# 6301_Lab3_Main.net
KiCad netlist of a schematic drawn in Altium Designer
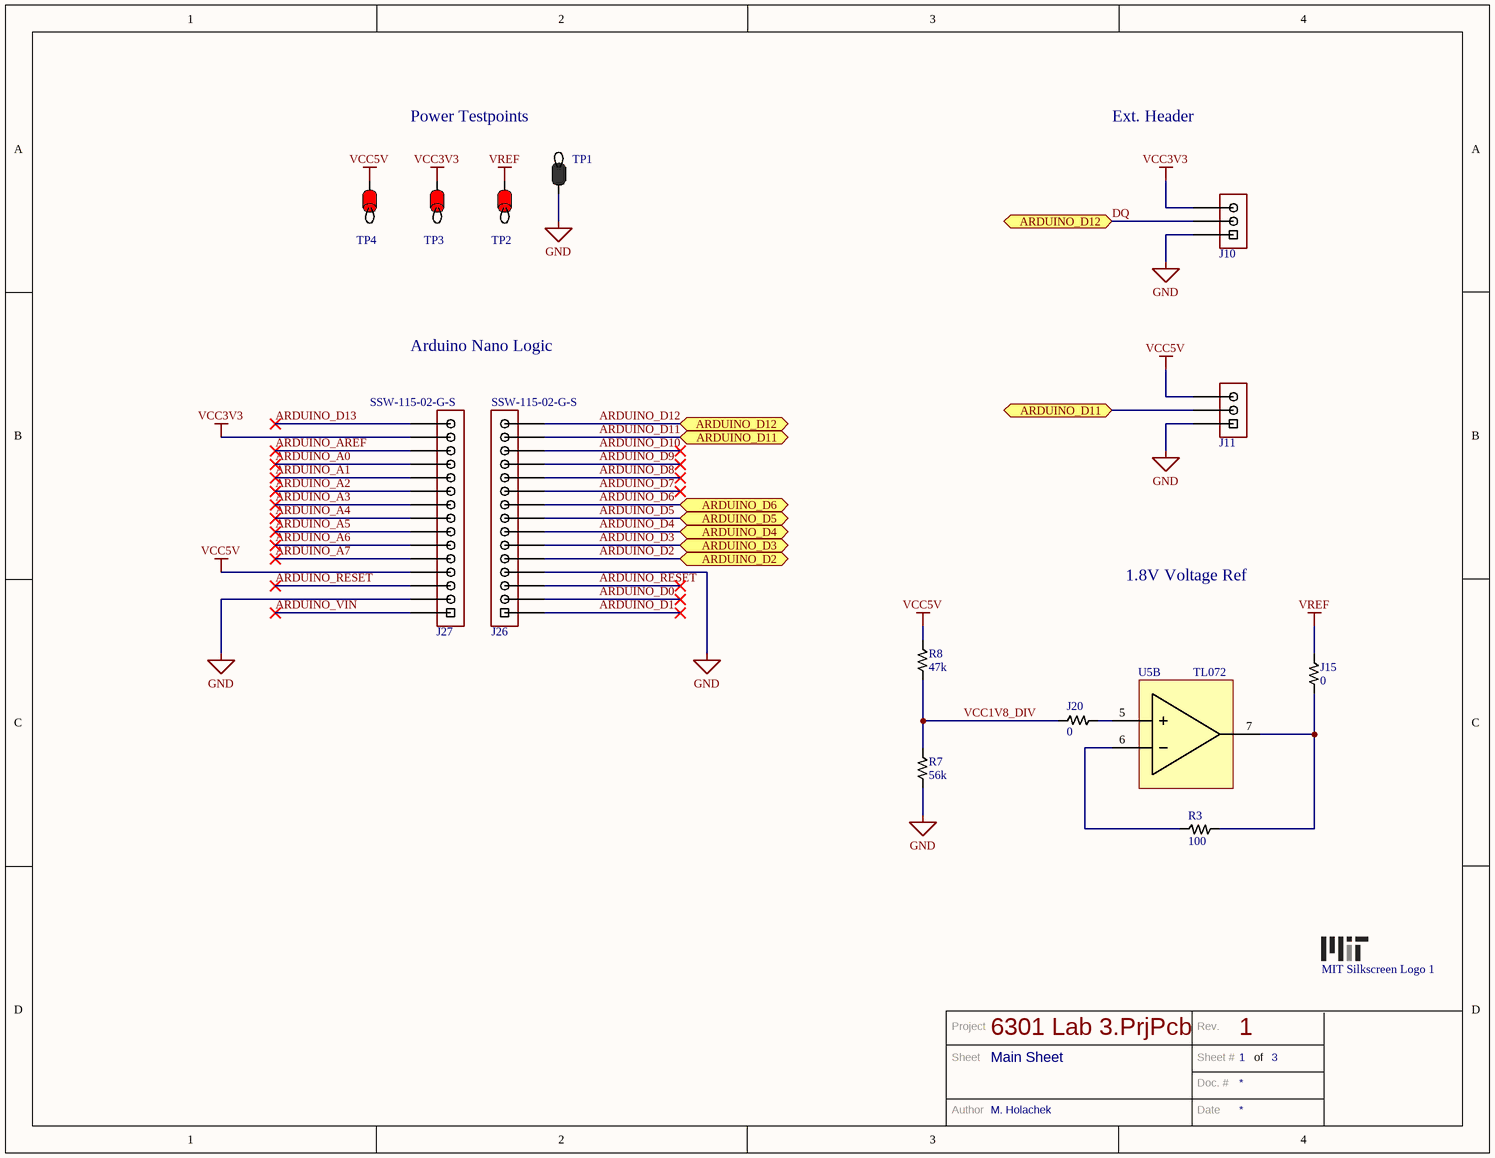
[diagram p0: 6301 Lab3 Main.SchDoc]

(export (version "E")
  (design (tool "Eeschema 10.0.6"))
  (components
    (comp (ref "J10")
      (value "Short")
      (footprint "1X03")
      (description "1x3 2.54mm Standard Connector")
      (libsource (lib "6301 Lab 3") (part "1x3"))
    )
    (comp (ref "J11")
      (value "Short")
      (footprint "1X03")
      (description "1x3 2.54mm Standard Connector")
      (libsource (lib "6301 Lab 3") (part "1x3"))
    )
    (comp (ref "J15")
      (value "0")
      (footprint "JUMP0402")
      (description "Jumper, 0402 Package")
      (libsource (lib "6301 Lab 3") (part "Jumper 0402"))
    )
    (comp (ref "J20")
      (value "0")
      (footprint "JUMP0402")
      (description "Jumper, 0402 Package")
      (libsource (lib "6301 Lab 3") (part "Jumper 0402"))
    )
    (comp (ref "J26")
      (value "SSW-115-02-G-S")
      (footprint "1x15")
      (description "1x15 2.54mm Standard Connector")
      (libsource (lib "6301 Lab 3") (part "1x15"))
    )
    (comp (ref "J27")
      (value "SSW-115-02-G-S")
      (footprint "1x15")
      (description "1x15 2.54mm Standard Connector")
      (libsource (lib "") (part "1x15_1"))
    )
    (comp (ref "MIT Silkscreen Logo 1")
      (value "MIT Logo")
      (footprint "MITLOGO")
      (libsource (lib "General") (part "MIT Logo"))
    )
    (comp (ref "R3")
      (value "100")
      (footprint "RES0805")
      (description "Resistor, 0805 Package")
      (fields (field (name "TOLERANCE") "1%"))
      (libsource (lib "6301 Lab 3") (part "Resistor"))
    )
    (comp (ref "R7")
      (value "56k")
      (footprint "RES0805")
      (description "Resistor, 0805 Package")
      (fields (field (name "TOLERANCE") "0.1%"))
      (libsource (lib "6301 Lab 3") (part "Resistor"))
    )
    (comp (ref "R8")
      (value "47k")
      (footprint "RES0805")
      (description "Resistor, 0805 Package")
      (fields (field (name "TOLERANCE") "1%"))
      (libsource (lib "6301 Lab 3") (part "Resistor"))
    )
    (comp (ref "TP1")
      (value "Black")
      (footprint "TP_BLACK")
      (description "Black Test Point")
      (libsource (lib "6301 Lab 3") (part "Black Test Point"))
    )
    (comp (ref "TP2")
      (value "Red")
      (footprint "TP_RED")
      (description "Red Test Point")
      (libsource (lib "6301 Lab 3") (part "Red Test Point"))
    )
    (comp (ref "TP3")
      (value "Red")
      (footprint "TP_RED")
      (description "Red Test Point")
      (libsource (lib "6301 Lab 3") (part "Red Test Point"))
    )
    (comp (ref "TP4")
      (value "Red")
      (footprint "TP_RED")
      (description "Red Test Point")
      (libsource (lib "6301 Lab 3") (part "Red Test Point"))
    )
    (comp (ref "U5")
      (value "TL072")
      (footprint "SOIC8")
      (description "Dual Low-Noise JFET-Input Op Amp")
      (libsource (lib "6301 Lab 3") (part "TL07xx"))
    )
  )
  (nets
    (net (code "1") (name "/ARDUINO_A0") (class "Default")
      (node (ref "J27") (pin "12") (pinfunction "12_12") (pintype "passive+no_connect"))
    )
    (net (code "2") (name "/ARDUINO_A1") (class "Default")
      (node (ref "J27") (pin "11") (pinfunction "11_11") (pintype "passive+no_connect"))
    )
    (net (code "3") (name "/ARDUINO_A2") (class "Default")
      (node (ref "J27") (pin "10") (pinfunction "10_10") (pintype "passive+no_connect"))
    )
    (net (code "4") (name "/ARDUINO_A3") (class "Default")
      (node (ref "J27") (pin "9") (pinfunction "9_9") (pintype "passive+no_connect"))
    )
    (net (code "5") (name "/ARDUINO_A4") (class "Default")
      (node (ref "J27") (pin "8") (pinfunction "8_8") (pintype "passive+no_connect"))
    )
    (net (code "6") (name "/ARDUINO_A5") (class "Default")
      (node (ref "J27") (pin "7") (pinfunction "7_7") (pintype "passive+no_connect"))
    )
    (net (code "7") (name "/ARDUINO_A6") (class "Default")
      (node (ref "J27") (pin "6") (pinfunction "6_6") (pintype "passive+no_connect"))
    )
    (net (code "8") (name "/ARDUINO_A7") (class "Default")
      (node (ref "J27") (pin "5") (pinfunction "5_5") (pintype "passive+no_connect"))
    )
    (net (code "9") (name "/ARDUINO_AREF") (class "Default")
      (node (ref "J27") (pin "13") (pinfunction "13_13") (pintype "passive+no_connect"))
    )
    (net (code "10") (name "/ARDUINO_D0") (class "Default")
      (node (ref "J26") (pin "2") (pinfunction "2_2") (pintype "passive+no_connect"))
    )
    (net (code "11") (name "/ARDUINO_D1") (class "Default")
      (node (ref "J26") (pin "1") (pinfunction "1_1") (pintype "passive+no_connect"))
    )
    (net (code "12") (name "/ARDUINO_D2") (class "Default")
      (node (ref "J26") (pin "5") (pinfunction "5_5") (pintype "passive"))
    )
    (net (code "13") (name "/ARDUINO_D3") (class "Default")
      (node (ref "J26") (pin "6") (pinfunction "6_6") (pintype "passive"))
    )
    (net (code "14") (name "/ARDUINO_D4") (class "Default")
      (node (ref "J26") (pin "7") (pinfunction "7_7") (pintype "passive"))
    )
    (net (code "15") (name "/ARDUINO_D5") (class "Default")
      (node (ref "J26") (pin "8") (pinfunction "8_8") (pintype "passive"))
    )
    (net (code "16") (name "/ARDUINO_D6") (class "Default")
      (node (ref "J26") (pin "9") (pinfunction "9_9") (pintype "passive"))
    )
    (net (code "17") (name "/ARDUINO_D7") (class "Default")
      (node (ref "J26") (pin "10") (pinfunction "10_10") (pintype "passive+no_connect"))
    )
    (net (code "18") (name "/ARDUINO_D8") (class "Default")
      (node (ref "J26") (pin "11") (pinfunction "11_11") (pintype "passive+no_connect"))
    )
    (net (code "19") (name "/ARDUINO_D9") (class "Default")
      (node (ref "J26") (pin "12") (pinfunction "12_12") (pintype "passive+no_connect"))
    )
    (net (code "20") (name "/ARDUINO_D10") (class "Default")
      (node (ref "J26") (pin "13") (pinfunction "13_13") (pintype "passive+no_connect"))
    )
    (net (code "21") (name "/ARDUINO_D11") (class "Default")
      (node (ref "J11") (pin "2") (pinfunction "2_2") (pintype "passive"))
      (node (ref "J26") (pin "14") (pinfunction "14_14") (pintype "passive"))
    )
    (net (code "22") (name "/ARDUINO_D12") (class "Default")
      (node (ref "J10") (pin "2") (pinfunction "2_2") (pintype "passive"))
      (node (ref "J26") (pin "15") (pinfunction "15_15") (pintype "passive"))
    )
    (net (code "23") (name "/ARDUINO_D13") (class "Default")
      (node (ref "J27") (pin "15") (pinfunction "15_15") (pintype "passive+no_connect"))
    )
    (net (code "24") (name "/ARDUINO_RESET") (class "Default")
      (node (ref "J26") (pin "3") (pinfunction "3_3") (pintype "passive"))
      (node (ref "J27") (pin "3") (pinfunction "3_3") (pintype "passive"))
    )
    (net (code "25") (name "/ARDUINO_VIN") (class "Default")
      (node (ref "J27") (pin "1") (pinfunction "1_1") (pintype "passive+no_connect"))
    )
    (net (code "26") (name "/VCC1V8_DIV") (class "Default")
      (node (ref "J20") (pin "1") (pinfunction "1_1") (pintype "passive"))
      (node (ref "R7") (pin "2") (pinfunction "2_2") (pintype "passive"))
      (node (ref "R8") (pin "1") (pinfunction "1_1") (pintype "passive"))
    )
    (net (code "27") (name "GND") (class "Default")
      (node (ref "J10") (pin "1") (pinfunction "1_1") (pintype "passive"))
      (node (ref "J11") (pin "1") (pinfunction "1_1") (pintype "passive"))
      (node (ref "J26") (pin "4") (pinfunction "4_4") (pintype "passive"))
      (node (ref "J27") (pin "2") (pinfunction "2_2") (pintype "passive"))
      (node (ref "R7") (pin "1") (pinfunction "1_1") (pintype "passive"))
      (node (ref "TP1") (pin "1") (pinfunction "1_1") (pintype "passive"))
    )
    (net (code "28") (name "Net-(U5B-2IN+)") (class "Default")
      (node (ref "J20") (pin "2") (pinfunction "2_2") (pintype "passive"))
      (node (ref "U5") (pin "5") (pinfunction "2IN+_5") (pintype "passive"))
    )
    (net (code "29") (name "Net-(U5B-2IN-)") (class "Default")
      (node (ref "R3") (pin "2") (pinfunction "2_2") (pintype "passive"))
      (node (ref "U5") (pin "6") (pinfunction "2IN-_6") (pintype "passive"))
    )
    (net (code "30") (name "Net-(U5B-2OUT)") (class "Default")
      (node (ref "J15") (pin "1") (pinfunction "1_1") (pintype "passive"))
      (node (ref "R3") (pin "1") (pinfunction "1_1") (pintype "passive"))
      (node (ref "U5") (pin "7") (pinfunction "2OUT_7") (pintype "passive"))
    )
    (net (code "31") (name "VCC3V3") (class "Default")
      (node (ref "J10") (pin "3") (pinfunction "3_3") (pintype "passive"))
      (node (ref "J27") (pin "14") (pinfunction "14_14") (pintype "passive"))
      (node (ref "TP3") (pin "1") (pinfunction "1_1") (pintype "passive"))
    )
    (net (code "32") (name "VCC5V") (class "Default")
      (node (ref "J11") (pin "3") (pinfunction "3_3") (pintype "passive"))
      (node (ref "J27") (pin "4") (pinfunction "4_4") (pintype "passive"))
      (node (ref "R8") (pin "2") (pinfunction "2_2") (pintype "passive"))
      (node (ref "TP4") (pin "1") (pinfunction "1_1") (pintype "passive"))
    )
    (net (code "33") (name "VREF") (class "Default")
      (node (ref "J15") (pin "2") (pinfunction "2_2") (pintype "passive"))
      (node (ref "TP2") (pin "1") (pinfunction "1_1") (pintype "passive"))
    )
  )
)
